# pr.net
KiCad netlist of a schematic drawn in EasyEDA
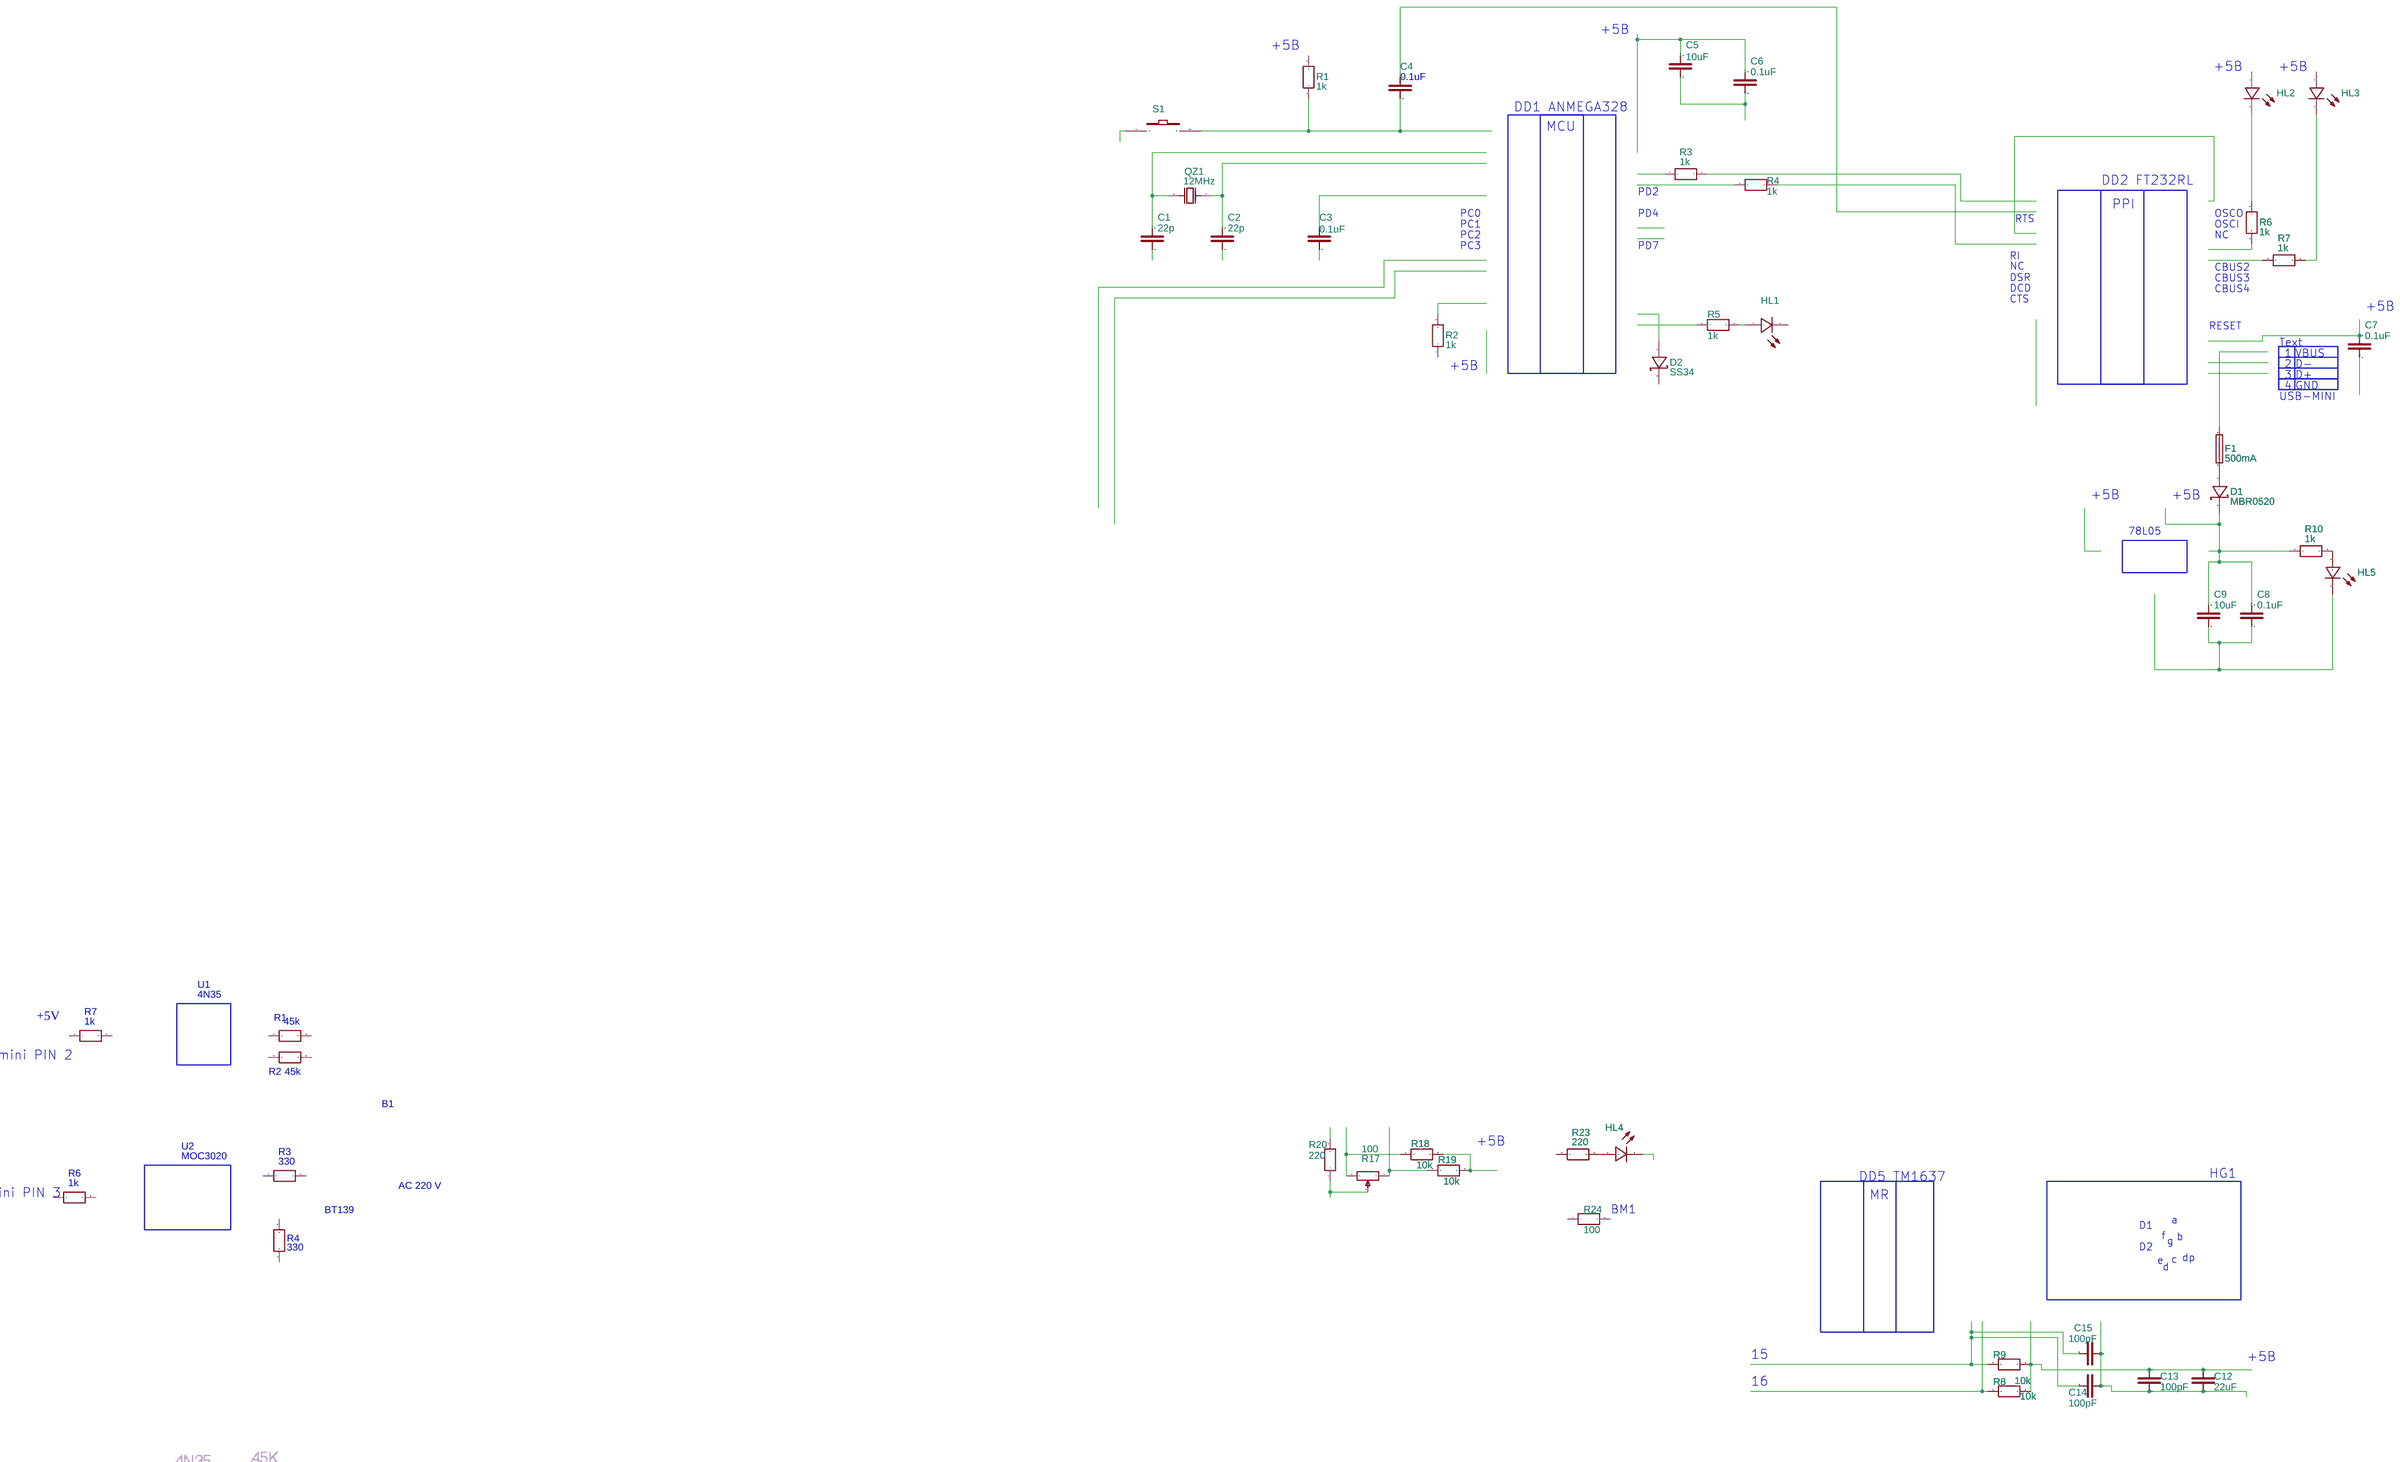
[diagram p0: schematic sheet]

(export (version "E")
  (design (tool "Eeschema 10.0.6"))
  (components
    (comp (ref "C1")
      (value "22p")
      (fields (field (name "BOM_Manufacturer Part") "?"))
      (libsource (lib "") (part "Unknown_75_-1080"))
    )
    (comp (ref "C2")
      (value "22p")
      (fields (field (name "BOM_Manufacturer Part") "?"))
      (libsource (lib "") (part "Unknown_140_-1080"))
    )
    (comp (ref "C3")
      (value "0.1uF")
      (fields (field (name "BOM_Manufacturer Part") "?"))
      (libsource (lib "") (part "Unknown_230_-1080"))
    )
    (comp (ref "C4")
      (value "Condensator1")
      (fields (field (name "BOM_Manufacturer Part") "?"))
      (libsource (lib "") (part "Unknown_305_-1220"))
    )
    (comp (ref "C5")
      (value "10uF")
      (fields (field (name "BOM_Manufacturer Part") "?"))
      (libsource (lib "") (part "Unknown_565_-1240"))
    )
    (comp (ref "C6")
      (value "0.1uF")
      (fields (field (name "BOM_Manufacturer Part") "?"))
      (libsource (lib "") (part "Unknown_625_-1225"))
    )
    (comp (ref "C7")
      (value "0.1uF")
      (fields (field (name "BOM_Manufacturer Part") "?"))
      (libsource (lib "") (part "Unknown_1195_-980"))
    )
    (comp (ref "C8")
      (value "0.1uF")
      (fields (field (name "BOM_Manufacturer Part") "?"))
      (libsource (lib "") (part "Unknown_1095_-730"))
    )
    (comp (ref "C9")
      (value "10uF")
      (fields (field (name "BOM_Manufacturer Part") "?"))
      (libsource (lib "") (part "Unknown_1055_-730"))
    )
    (comp (ref "C12")
      (value "22uF")
      (fields (field (name "BOM_Manufacturer Part") "?"))
      (libsource (lib "") (part "Unknown_1050_-20"))
    )
    (comp (ref "C13")
      (value "100pF")
      (fields (field (name "BOM_Manufacturer Part") "?"))
      (libsource (lib "") (part "Unknown_1000_-20"))
    )
    (comp (ref "C14")
      (value "100pF")
      (fields (field (name "BOM_Manufacturer Part") "?"))
      (libsource (lib "") (part "Unknown_945_-15"))
    )
    (comp (ref "C15")
      (value "100pF")
      (fields (field (name "BOM_Manufacturer Part") "?"))
      (libsource (lib "") (part "Unknown_945_-45"))
    )
    (comp (ref "D1")
      (value "MBR0520")
      (fields (field (name "BOM_Manufacturer Part") "SS34") (field (name "BOM_Supplier Part") "C8678"))
      (libsource (lib "") (part "Unknown_1065_-845"))
    )
    (comp (ref "D2")
      (value "SS34")
      (fields (field (name "BOM_Supplier Part") "C8678"))
      (libsource (lib "") (part "Unknown_545_-965"))
    )
    (comp (ref "F1")
      (value "500mA")
      (fields
        (field (name "BOM_Manufacturer Part") "Glass tube fuse2A 3F 250VAC")
        (field (name "BOM_Supplier Part") "C71017")
      )
      (libsource (lib "") (part "Unknown_1065_-885"))
    )
    (comp (ref "HL1")
      (value "LED-3MM")
      (fields
        (field (name "BOM_Manufacturer Part") "204-10SURD/S530-A3")
        (field (name "BOM_Supplier Part") "C99772")
      )
      (libsource (lib "") (part "Unknown_645_-995"))
    )
    (comp (ref "HL2")
      (value "LED-3MM")
      (fields
        (field (name "BOM_Manufacturer Part") "204-10SURD/S530-A3")
        (field (name "BOM_Supplier Part") "C99772")
      )
      (libsource (lib "") (part "Unknown_1100_-1215"))
    )
    (comp (ref "HL3")
      (value "LED-3MM")
      (fields
        (field (name "BOM_Manufacturer Part") "204-10SURD/S530-A3")
        (field (name "BOM_Supplier Part") "C99772")
      )
      (libsource (lib "") (part "Unknown_1160_-1215"))
    )
    (comp (ref "HL4")
      (value "LED-3MM")
      (fields
        (field (name "BOM_Manufacturer Part") "204-10SURD/S530-A3")
        (field (name "BOM_Supplier Part") "C99772")
      )
      (libsource (lib "") (part "Unknown_510_-235"))
    )
    (comp (ref "HL5")
      (value "LED-3MM")
      (fields
        (field (name "BOM_Manufacturer Part") "204-10SURD/S530-A3")
        (field (name "BOM_Supplier Part") "C99772")
      )
      (libsource (lib "") (part "Unknown_1175_-770"))
    )
    (comp (ref "QZ1")
      (value "12MHz")
      (fields
        (field (name "BOM_Manufacturer Part") "X49SD12MSD2SC")
        (field (name "BOM_Supplier Part") "C16369")
      )
      (libsource (lib "") (part "X49SD12MSD2SC"))
    )
    (comp (ref "R1")
      (value "1k")
      (fields (field (name "BOM_Manufacturer Part") "?"))
      (libsource (lib "") (part "Res_AXIAL-0.3(1/8W)_EU_2"))
    )
    (comp (ref "R2")
      (value "1k")
      (fields (field (name "BOM_Manufacturer Part") "?"))
      (libsource (lib "") (part "Res_AXIAL-0.3(1/8W)_EU_2"))
    )
    (comp (ref "R3")
      (value "1k")
      (fields (field (name "BOM_Manufacturer Part") "?"))
      (libsource (lib "") (part "Res_AXIAL-0.3(1/8W)_EU"))
    )
    (comp (ref "R4")
      (value "1k")
      (fields (field (name "BOM_Manufacturer Part") "?"))
      (libsource (lib "") (part "Res_AXIAL-0.3(1/8W)_EU"))
    )
    (comp (ref "R5")
      (value "1k")
      (fields (field (name "BOM_Manufacturer Part") "?"))
      (libsource (lib "") (part "Res_AXIAL-0.3(1/8W)_EU_1"))
    )
    (comp (ref "R6")
      (value "1k")
      (fields (field (name "BOM_Manufacturer Part") "?"))
      (libsource (lib "") (part "Res_AXIAL-0.3(1/8W)_EU_3"))
    )
    (comp (ref "R7")
      (value "1k")
      (fields (field (name "BOM_Manufacturer Part") "?"))
      (libsource (lib "") (part "Res_AXIAL-0.3(1/8W)_EU_1"))
    )
    (comp (ref "R8")
      (value "10k")
      (fields (field (name "BOM_Manufacturer Part") "?"))
      (libsource (lib "") (part "Res_AXIAL-0.3(1/8W)_EU_1"))
    )
    (comp (ref "R9")
      (value "10k")
      (fields (field (name "BOM_Manufacturer Part") "?"))
      (libsource (lib "") (part "Res_AXIAL-0.3(1/8W)_EU_1"))
    )
    (comp (ref "R10") (value "1k") (libsource (lib "") (part "Res_AXIAL-0.3(1/8W)_EU_1")))
    (comp (ref "R12") (value "1k") (libsource (lib "") (part "Res_AXIAL-0.3(1/8W)_EU_1")))
    (comp (ref "R13") (value "1k") (libsource (lib "") (part "Res_AXIAL-0.3(1/8W)_EU_1")))
    (comp (ref "R14") (value "1k") (libsource (lib "") (part "Res_AXIAL-0.3(1/8W)_EU_1")))
    (comp (ref "R15") (value "1k") (libsource (lib "") (part "Res_AXIAL-0.3(1/8W)_EU_2")))
    (comp (ref "R16") (value "1k") (libsource (lib "") (part "Res_AXIAL-0.3(1/8W)_EU_1")))
    (comp (ref "R17")
      (value "100")
      (fields
        (field (name "BOM_Manufacturer Part") "3386P-1-101LF")
        (field (name "BOM_Supplier Part") "C125022")
      )
      (libsource (lib "") (part "3386P-1-101LF"))
    )
    (comp (ref "R18")
      (value "10k")
      (fields (field (name "BOM_Manufacturer Part") "?"))
      (libsource (lib "") (part "Res_AXIAL-0.3(1/8W)_EU_1"))
    )
    (comp (ref "R19")
      (value "10k")
      (fields (field (name "BOM_Manufacturer Part") "?"))
      (libsource (lib "") (part "Res_AXIAL-0.3(1/8W)_EU_1"))
    )
    (comp (ref "R20")
      (value "220")
      (fields (field (name "BOM_Manufacturer Part") "?"))
      (libsource (lib "") (part "Res_AXIAL-0.3(1/8W)_EU_2"))
    )
    (comp (ref "R21") (value "1k") (libsource (lib "") (part "Res_AXIAL-0.3(1/8W)_EU_1")))
    (comp (ref "R23")
      (value "220")
      (fields (field (name "BOM_Manufacturer Part") "?"))
      (libsource (lib "") (part "Res_AXIAL-0.3(1/8W)_EU_1"))
    )
    (comp (ref "R24")
      (value "100")
      (fields (field (name "BOM_Manufacturer Part") "?"))
      (libsource (lib "") (part "Res_AXIAL-0.3(1/8W)_EU_1"))
    )
    (comp (ref "S1")
      (value "EVQ22705R")
      (fields (field (name "BOM_Supplier Part") "C79156"))
      (libsource (lib "") (part "Unknown_85_-1180"))
    )
  )
  (nets
    (net (code "1") (name "Net-(C4-PadP$1)") (class "Default")
      (node (ref "C4") (pin "P$1") (pinfunction "P$1_P$1") (pintype "unspecified"))
      (node (ref "R1") (pin "1") (pinfunction "1_1") (pintype "unspecified"))
      (node (ref "S1") (pin "2") (pinfunction "2_2") (pintype "input"))
    )
    (net (code "2") (name "Net-(C5-PadP$1)") (class "Default")
      (node (ref "C5") (pin "P$1") (pinfunction "P$1_P$1") (pintype "unspecified"))
      (node (ref "C6") (pin "P$1") (pinfunction "P$1_P$1") (pintype "unspecified"))
    )
    (net (code "3") (name "Net-(C5-PadP$2)") (class "Default")
      (node (ref "C5") (pin "P$2") (pinfunction "P$2_P$2") (pintype "unspecified"))
      (node (ref "C6") (pin "P$2") (pinfunction "P$2_P$2") (pintype "unspecified"))
    )
    (net (code "4") (name "Net-(C12-PadP$1)") (class "Default")
      (node (ref "C12") (pin "P$1") (pinfunction "P$1_P$1") (pintype "unspecified"))
      (node (ref "C13") (pin "P$2") (pinfunction "P$2_P$2") (pintype "unspecified"))
      (node (ref "C14") (pin "P$1") (pinfunction "P$1_P$1") (pintype "unspecified"))
      (node (ref "C15") (pin "P$1") (pinfunction "P$1_P$1") (pintype "unspecified"))
    )
    (net (code "5") (name "Net-(C12-PadP$2)") (class "Default")
      (node (ref "C12") (pin "P$2") (pinfunction "P$2_P$2") (pintype "unspecified"))
      (node (ref "C13") (pin "P$1") (pinfunction "P$1_P$1") (pintype "unspecified"))
      (node (ref "R8") (pin "2") (pinfunction "2_2") (pintype "unspecified"))
      (node (ref "R9") (pin "2") (pinfunction "2_2") (pintype "unspecified"))
    )
    (net (code "6") (name "Net-(C14-PadP$2)") (class "Default")
      (node (ref "C14") (pin "P$2") (pinfunction "P$2_P$2") (pintype "unspecified"))
      (node (ref "C15") (pin "P$2") (pinfunction "P$2_P$2") (pintype "unspecified"))
      (node (ref "R9") (pin "1") (pinfunction "1_1") (pintype "unspecified"))
    )
    (net (code "7") (name "Net-(D1-A)") (class "Default")
      (node (ref "D1") (pin "1") (pinfunction "A_1") (pintype "unspecified"))
      (node (ref "F1") (pin "1") (pinfunction "1_1") (pintype "unspecified"))
    )
    (net (code "8") (name "Net-(D1-K)") (class "Default")
      (node (ref "C8") (pin "P$2") (pinfunction "P$2_P$2") (pintype "unspecified"))
      (node (ref "C9") (pin "P$2") (pinfunction "P$2_P$2") (pintype "unspecified"))
      (node (ref "D1") (pin "2") (pinfunction "K_2") (pintype "unspecified"))
      (node (ref "R10") (pin "1") (pinfunction "1_1") (pintype "unspecified"))
    )
    (net (code "9") (name "Net-(HL1-+)") (class "Default")
      (node (ref "HL1") (pin "1") (pinfunction "+_1") (pintype "unspecified"))
      (node (ref "R5") (pin "2") (pinfunction "2_2") (pintype "unspecified"))
    )
    (net (code "10") (name "Net-(HL2--)") (class "Default")
      (node (ref "HL2") (pin "2") (pinfunction "-_2") (pintype "unspecified"))
      (node (ref "R6") (pin "1") (pinfunction "1_1") (pintype "unspecified"))
    )
    (net (code "11") (name "Net-(HL3--)") (class "Default")
      (node (ref "HL3") (pin "2") (pinfunction "-_2") (pintype "unspecified"))
      (node (ref "R7") (pin "2") (pinfunction "2_2") (pintype "unspecified"))
    )
    (net (code "12") (name "Net-(HL4-+)") (class "Default")
      (node (ref "HL4") (pin "1") (pinfunction "+_1") (pintype "unspecified"))
      (node (ref "R23") (pin "2") (pinfunction "2_2") (pintype "unspecified"))
    )
    (net (code "13") (name "Net-(HL5-+)") (class "Default")
      (node (ref "HL5") (pin "1") (pinfunction "+_1") (pintype "unspecified"))
      (node (ref "R10") (pin "2") (pinfunction "2_2") (pintype "unspecified"))
    )
    (net (code "14") (name "Net-(HL5--)") (class "Default")
      (node (ref "C8") (pin "P$1") (pinfunction "P$1_P$1") (pintype "unspecified"))
      (node (ref "C9") (pin "P$1") (pinfunction "P$1_P$1") (pintype "unspecified"))
      (node (ref "HL5") (pin "2") (pinfunction "-_2") (pintype "unspecified"))
    )
    (net (code "15") (name "Net-(QZ1-OSC1)") (class "Default")
      (node (ref "C2") (pin "P$2") (pinfunction "P$2_P$2") (pintype "unspecified"))
      (node (ref "QZ1") (pin "1") (pinfunction "OSC1_1") (pintype "input"))
    )
    (net (code "16") (name "Net-(QZ1-OSC2)") (class "Default")
      (node (ref "C1") (pin "P$2") (pinfunction "P$2_P$2") (pintype "unspecified"))
      (node (ref "QZ1") (pin "2") (pinfunction "OSC2_2") (pintype "input"))
    )
    (net (code "17") (name "Net-(R17-Pad1)") (class "Default")
      (node (ref "R17") (pin "1") (pinfunction "1_1") (pintype "input"))
      (node (ref "R19") (pin "1") (pinfunction "1_1") (pintype "unspecified"))
    )
    (net (code "18") (name "Net-(R17-Pad2)") (class "Default")
      (node (ref "R17") (pin "2") (pinfunction "2_2") (pintype "input"))
      (node (ref "R20") (pin "1") (pinfunction "1_1") (pintype "unspecified"))
    )
    (net (code "19") (name "Net-(R17-Pad3)") (class "Default")
      (node (ref "R17") (pin "3") (pinfunction "3_3") (pintype "input"))
      (node (ref "R18") (pin "1") (pinfunction "1_1") (pintype "unspecified"))
    )
    (net (code "20") (name "Net-(R18-Pad2)") (class "Default")
      (node (ref "R18") (pin "2") (pinfunction "2_2") (pintype "unspecified"))
      (node (ref "R19") (pin "2") (pinfunction "2_2") (pintype "unspecified"))
    )
    (net (code "21") (name "unconnected-(C1-PadP$1)") (class "Default")
      (node (ref "C1") (pin "P$1") (pinfunction "P$1_P$1") (pintype "unspecified"))
    )
    (net (code "22") (name "unconnected-(C2-PadP$1)") (class "Default")
      (node (ref "C2") (pin "P$1") (pinfunction "P$1_P$1") (pintype "unspecified"))
    )
    (net (code "23") (name "unconnected-(C3-PadP$1)") (class "Default")
      (node (ref "C3") (pin "P$1") (pinfunction "P$1_P$1") (pintype "unspecified"))
    )
    (net (code "24") (name "unconnected-(C3-PadP$2)") (class "Default")
      (node (ref "C3") (pin "P$2") (pinfunction "P$2_P$2") (pintype "unspecified"))
    )
    (net (code "25") (name "unconnected-(C4-PadP$2)") (class "Default")
      (node (ref "C4") (pin "P$2") (pinfunction "P$2_P$2") (pintype "unspecified"))
    )
    (net (code "26") (name "unconnected-(C7-PadP$1)") (class "Default")
      (node (ref "C7") (pin "P$1") (pinfunction "P$1_P$1") (pintype "unspecified"))
    )
    (net (code "27") (name "unconnected-(C7-PadP$2)") (class "Default")
      (node (ref "C7") (pin "P$2") (pinfunction "P$2_P$2") (pintype "unspecified"))
    )
    (net (code "28") (name "unconnected-(D2-A-Pad1)") (class "Default")
      (node (ref "D2") (pin "1") (pinfunction "A_1") (pintype "unspecified"))
    )
    (net (code "29") (name "unconnected-(D2-K-Pad2)") (class "Default")
      (node (ref "D2") (pin "2") (pinfunction "K_2") (pintype "unspecified"))
    )
    (net (code "30") (name "unconnected-(F1-Pad2)") (class "Default")
      (node (ref "F1") (pin "2") (pinfunction "2_2") (pintype "unspecified"))
    )
    (net (code "31") (name "unconnected-(HL1---Pad2)") (class "Default")
      (node (ref "HL1") (pin "2") (pinfunction "-_2") (pintype "unspecified"))
    )
    (net (code "32") (name "unconnected-(HL2-+-Pad1)") (class "Default")
      (node (ref "HL2") (pin "1") (pinfunction "+_1") (pintype "unspecified"))
    )
    (net (code "33") (name "unconnected-(HL3-+-Pad1)") (class "Default")
      (node (ref "HL3") (pin "1") (pinfunction "+_1") (pintype "unspecified"))
    )
    (net (code "34") (name "unconnected-(HL4---Pad2)") (class "Default")
      (node (ref "HL4") (pin "2") (pinfunction "-_2") (pintype "unspecified"))
    )
    (net (code "35") (name "unconnected-(R1-Pad2)") (class "Default")
      (node (ref "R1") (pin "2") (pinfunction "2_2") (pintype "unspecified"))
    )
    (net (code "36") (name "unconnected-(R2-Pad1)") (class "Default")
      (node (ref "R2") (pin "1") (pinfunction "1_1") (pintype "unspecified"))
    )
    (net (code "37") (name "unconnected-(R2-Pad2)") (class "Default")
      (node (ref "R2") (pin "2") (pinfunction "2_2") (pintype "unspecified"))
    )
    (net (code "38") (name "unconnected-(R3-Pad1)") (class "Default")
      (node (ref "R3") (pin "1") (pinfunction "1_1") (pintype "unspecified"))
    )
    (net (code "39") (name "unconnected-(R3-Pad2)") (class "Default")
      (node (ref "R3") (pin "2") (pinfunction "2_2") (pintype "unspecified"))
    )
    (net (code "40") (name "unconnected-(R4-Pad1)") (class "Default")
      (node (ref "R4") (pin "1") (pinfunction "1_1") (pintype "unspecified"))
    )
    (net (code "41") (name "unconnected-(R4-Pad2)") (class "Default")
      (node (ref "R4") (pin "2") (pinfunction "2_2") (pintype "unspecified"))
    )
    (net (code "42") (name "unconnected-(R5-Pad1)") (class "Default")
      (node (ref "R5") (pin "1") (pinfunction "1_1") (pintype "unspecified"))
    )
    (net (code "43") (name "unconnected-(R6-Pad2)") (class "Default")
      (node (ref "R6") (pin "2") (pinfunction "2_2") (pintype "unspecified"))
    )
    (net (code "44") (name "unconnected-(R7-Pad1)") (class "Default")
      (node (ref "R7") (pin "1") (pinfunction "1_1") (pintype "unspecified"))
    )
    (net (code "45") (name "unconnected-(R8-Pad1)") (class "Default")
      (node (ref "R8") (pin "1") (pinfunction "1_1") (pintype "unspecified"))
    )
    (net (code "46") (name "unconnected-(R12-Pad1)") (class "Default")
      (node (ref "R12") (pin "1") (pinfunction "1_1") (pintype "unspecified"))
    )
    (net (code "47") (name "unconnected-(R12-Pad2)") (class "Default")
      (node (ref "R12") (pin "2") (pinfunction "2_2") (pintype "unspecified"))
    )
    (net (code "48") (name "unconnected-(R13-Pad1)") (class "Default")
      (node (ref "R13") (pin "1") (pinfunction "1_1") (pintype "unspecified"))
    )
    (net (code "49") (name "unconnected-(R13-Pad2)") (class "Default")
      (node (ref "R13") (pin "2") (pinfunction "2_2") (pintype "unspecified"))
    )
    (net (code "50") (name "unconnected-(R14-Pad1)") (class "Default")
      (node (ref "R14") (pin "1") (pinfunction "1_1") (pintype "unspecified"))
    )
    (net (code "51") (name "unconnected-(R14-Pad2)") (class "Default")
      (node (ref "R14") (pin "2") (pinfunction "2_2") (pintype "unspecified"))
    )
    (net (code "52") (name "unconnected-(R15-Pad1)") (class "Default")
      (node (ref "R15") (pin "1") (pinfunction "1_1") (pintype "unspecified"))
    )
    (net (code "53") (name "unconnected-(R15-Pad2)") (class "Default")
      (node (ref "R15") (pin "2") (pinfunction "2_2") (pintype "unspecified"))
    )
    (net (code "54") (name "unconnected-(R16-Pad1)") (class "Default")
      (node (ref "R16") (pin "1") (pinfunction "1_1") (pintype "unspecified"))
    )
    (net (code "55") (name "unconnected-(R16-Pad2)") (class "Default")
      (node (ref "R16") (pin "2") (pinfunction "2_2") (pintype "unspecified"))
    )
    (net (code "56") (name "unconnected-(R20-Pad2)") (class "Default")
      (node (ref "R20") (pin "2") (pinfunction "2_2") (pintype "unspecified"))
    )
    (net (code "57") (name "unconnected-(R21-Pad1)") (class "Default")
      (node (ref "R21") (pin "1") (pinfunction "1_1") (pintype "unspecified"))
    )
    (net (code "58") (name "unconnected-(R21-Pad2)") (class "Default")
      (node (ref "R21") (pin "2") (pinfunction "2_2") (pintype "unspecified"))
    )
    (net (code "59") (name "unconnected-(R23-Pad1)") (class "Default")
      (node (ref "R23") (pin "1") (pinfunction "1_1") (pintype "unspecified"))
    )
    (net (code "60") (name "unconnected-(R24-Pad1)") (class "Default")
      (node (ref "R24") (pin "1") (pinfunction "1_1") (pintype "unspecified"))
    )
    (net (code "61") (name "unconnected-(R24-Pad2)") (class "Default")
      (node (ref "R24") (pin "2") (pinfunction "2_2") (pintype "unspecified"))
    )
    (net (code "62") (name "unconnected-(S1-Pad1)") (class "Default")
      (node (ref "S1") (pin "1") (pinfunction "1_1") (pintype "input"))
    )
  )
)
